# FFT-spectrum-analyser.net
KiCad netlist of a schematic drawn in EAGLE
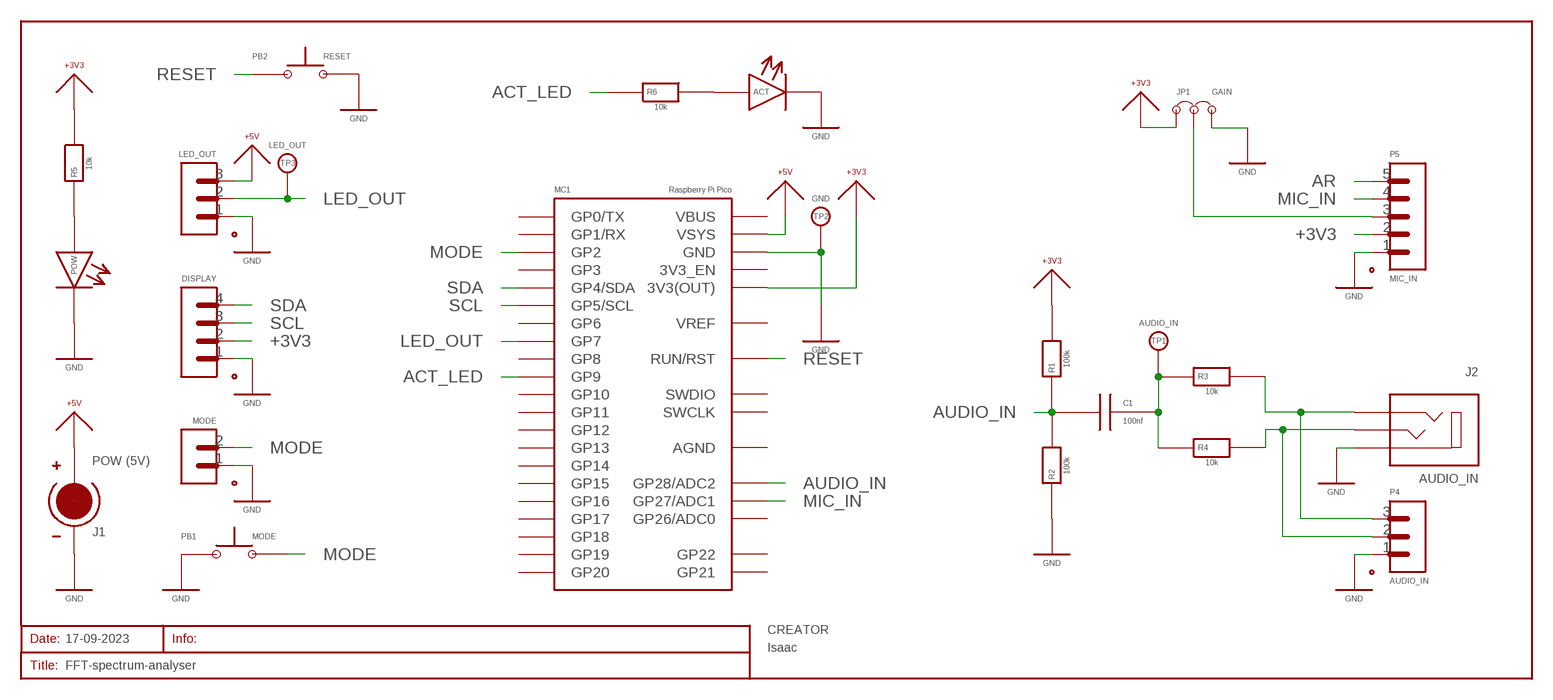
[diagram p0: schematic, sheet 1]

(export (version "E")
  (design (tool "Eeschema 10.0.6"))
  (components
    (comp (ref "ACT")
      (value "LED_3MM")
      (footprint "eagle-import:LED_3MM")
      (libsource (lib "eagle-import") (part "LED_3MM"))
    )
    (comp (ref "C1")
      (value "100nf")
      (footprint "eagle-import:CAPACITOR_UNPOLARISED_5.08MM")
      (libsource (lib "eagle-import") (part "CAPACITOR_UNPOLARISED_5.08MM"))
    )
    (comp (ref "CREATOR")
      (value "Isaac")
      (footprint "eagle-import:INFO_T")
      (libsource (lib "eagle-import") (part "INFO_T"))
    )
    (comp (ref "DISPLAY")
      (value "PORT_4-PIN_HEADER")
      (footprint "eagle-import:HEADER_4-PIN")
      (libsource (lib "eagle-import") (part "PORT_4-PIN_HEADER"))
    )
    (comp (ref "J1")
      (value "POW (5V)")
      (footprint "eagle-import:XH2.54_2-PIN")
      (libsource (lib "eagle-import") (part "DC_POWER_CENTER-POS_XH2.54"))
    )
    (comp (ref "J2")
      (value "AUDIO_IN")
      (footprint "eagle-import:3.5MM-JACK")
      (libsource (lib "eagle-import") (part "3.5MM-JACK_TYPE-A"))
    )
    (comp (ref "JP1")
      (value "GAIN")
      (footprint "eagle-import:HEADER_3-PIN_JUMPER")
      (libsource (lib "eagle-import") (part "JUMPER_3-WAY_HEADER"))
    )
    (comp (ref "LED_OUT")
      (value "PORT_3-PIN_XH2.54")
      (footprint "eagle-import:XH2.54_3-PIN")
      (libsource (lib "eagle-import") (part "PORT_3-PIN_XH2.54"))
    )
    (comp (ref "MC1")
      (value "RASPBERRY-PI-PICO_THT")
      (footprint "eagle-import:RASPBERRY-PI-PICO_THT")
      (libsource (lib "eagle-import") (part "RASPBERRY-PI-PICO_THT"))
    )
    (comp (ref "MODE")
      (value "PORT_2-PIN_XH2.54")
      (footprint "eagle-import:XH2.54_2-PIN")
      (libsource (lib "eagle-import") (part "PORT_2-PIN_XH2.54"))
    )
    (comp (ref "P4")
      (value "AUDIO_IN")
      (footprint "eagle-import:XH2.54_3-PIN")
      (libsource (lib "eagle-import") (part "PORT_3-PIN_XH2.54"))
    )
    (comp (ref "P5")
      (value "MIC_IN")
      (footprint "eagle-import:XH2.54_5-PIN")
      (libsource (lib "eagle-import") (part "PORT_5-PIN_XH2.54"))
    )
    (comp (ref "PB1")
      (value "MODE")
      (footprint "eagle-import:6MM_PUSHBUTTON")
      (libsource (lib "eagle-import") (part "MOMENTARY-SWITCH_NO_PUSHBUTTON"))
    )
    (comp (ref "PB2")
      (value "RESET")
      (footprint "eagle-import:6MM_PUSHBUTTON")
      (libsource (lib "eagle-import") (part "MOMENTARY-SWITCH_NO_PUSHBUTTON"))
    )
    (comp (ref "POW")
      (value "LED_3MM")
      (footprint "eagle-import:LED_3MM")
      (libsource (lib "eagle-import") (part "LED_3MM"))
    )
    (comp (ref "R1")
      (value "100k")
      (footprint "eagle-import:RESISTOR_10.16MM")
      (libsource (lib "eagle-import") (part "RESISTOR"))
    )
    (comp (ref "R2")
      (value "100k")
      (footprint "eagle-import:RESISTOR_10.16MM")
      (libsource (lib "eagle-import") (part "RESISTOR"))
    )
    (comp (ref "R3")
      (value "10k")
      (footprint "eagle-import:RESISTOR_10.16MM")
      (libsource (lib "eagle-import") (part "RESISTOR"))
    )
    (comp (ref "R4")
      (value "10k")
      (footprint "eagle-import:RESISTOR_10.16MM")
      (libsource (lib "eagle-import") (part "RESISTOR"))
    )
    (comp (ref "R5")
      (value "10k")
      (footprint "eagle-import:RESISTOR_10.16MM")
      (libsource (lib "eagle-import") (part "RESISTOR"))
    )
    (comp (ref "R6")
      (value "10k")
      (footprint "eagle-import:RESISTOR_10.16MM")
      (libsource (lib "eagle-import") (part "RESISTOR"))
    )
    (comp (ref "SCHEMATIC1")
      (value "17-09-2023")
      (footprint "eagle-import:SHEET")
      (libsource (lib "eagle-import") (part "SHEET"))
    )
    (comp (ref "TP1")
      (value "AUDIO_IN")
      (footprint "eagle-import:PAD_T")
      (libsource (lib "eagle-import") (part "TEST-POINT_T"))
    )
    (comp (ref "TP2")
      (value "GND")
      (footprint "eagle-import:PAD_T")
      (libsource (lib "eagle-import") (part "TEST-POINT_T"))
    )
    (comp (ref "TP3")
      (value "LED_OUT")
      (footprint "eagle-import:PAD_T")
      (libsource (lib "eagle-import") (part "TEST-POINT_T"))
    )
  )
  (nets
    (net (code "1") (name "+3V3") (class "Default")
      (node (ref "DISPLAY") (pin "2") (pinfunction "2_2") (pintype "bidirectional"))
      (node (ref "JP1") (pin "1") (pinfunction "1_1") (pintype "bidirectional"))
      (node (ref "MC1") (pin "36") (pinfunction "3V3(OUT)_36") (pintype "power_in"))
      (node (ref "P5") (pin "2") (pinfunction "2_2") (pintype "bidirectional"))
      (node (ref "R1") (pin "2") (pinfunction "2_2") (pintype "bidirectional"))
      (node (ref "R5") (pin "2") (pinfunction "2_2") (pintype "bidirectional"))
    )
    (net (code "2") (name "+5V") (class "Default")
      (node (ref "J1") (pin "2") (pinfunction "+_2") (pintype "output"))
      (node (ref "LED_OUT") (pin "3") (pinfunction "3_3") (pintype "bidirectional"))
      (node (ref "MC1") (pin "39") (pinfunction "VSYS_39") (pintype "bidirectional"))
    )
    (net (code "3") (name "/ACT_LED") (class "Default")
      (node (ref "MC1") (pin "12") (pinfunction "GP9_12") (pintype "bidirectional"))
      (node (ref "R6") (pin "1") (pinfunction "1_1") (pintype "bidirectional"))
    )
    (net (code "4") (name "/AGND") (class "Default")
      (node (ref "MC1") (pin "33") (pinfunction "AGND_33") (pintype "power_in"))
    )
    (net (code "5") (name "/AR") (class "Default")
      (node (ref "P5") (pin "5") (pinfunction "5_5") (pintype "bidirectional"))
    )
    (net (code "6") (name "/AUDIO_IN") (class "Default")
      (node (ref "C1") (pin "1") (pinfunction "1_1") (pintype "bidirectional"))
      (node (ref "MC1") (pin "34") (pinfunction "GP28/ADC2_34") (pintype "bidirectional"))
      (node (ref "R1") (pin "1") (pinfunction "1_1") (pintype "bidirectional"))
      (node (ref "R2") (pin "2") (pinfunction "2_2") (pintype "bidirectional"))
    )
    (net (code "7") (name "/LED_OUT") (class "Default")
      (node (ref "LED_OUT") (pin "2") (pinfunction "2_2") (pintype "bidirectional"))
      (node (ref "MC1") (pin "10") (pinfunction "GP7_10") (pintype "bidirectional"))
      (node (ref "TP3") (pin "1") (pinfunction "1_1") (pintype "bidirectional"))
    )
    (net (code "8") (name "/MIC_IN") (class "Default")
      (node (ref "MC1") (pin "32") (pinfunction "GP27/ADC1_32") (pintype "bidirectional"))
      (node (ref "P5") (pin "4") (pinfunction "4_4") (pintype "bidirectional"))
    )
    (net (code "9") (name "/MODE") (class "Default")
      (node (ref "MC1") (pin "4") (pinfunction "GP2_4") (pintype "bidirectional"))
      (node (ref "MODE") (pin "2") (pinfunction "2_2") (pintype "bidirectional"))
      (node (ref "PB1") (pin "2_A") (pinfunction "2_2_A") (pintype "bidirectional"))
      (node (ref "PB1") (pin "2_B") (pinfunction "2_2_B") (pintype "bidirectional"))
    )
    (net (code "10") (name "/RESET") (class "Default")
      (node (ref "MC1") (pin "30") (pinfunction "RUN/RST_30") (pintype "bidirectional"))
      (node (ref "PB2") (pin "1_A") (pinfunction "1_1_A") (pintype "bidirectional"))
      (node (ref "PB2") (pin "1_B") (pinfunction "1_1_B") (pintype "bidirectional"))
    )
    (net (code "11") (name "/SCL") (class "Default")
      (node (ref "DISPLAY") (pin "3") (pinfunction "3_3") (pintype "bidirectional"))
      (node (ref "MC1") (pin "7") (pinfunction "GP5/SCL_7") (pintype "bidirectional"))
    )
    (net (code "12") (name "/SDA") (class "Default")
      (node (ref "DISPLAY") (pin "4") (pinfunction "4_4") (pintype "bidirectional"))
      (node (ref "MC1") (pin "6") (pinfunction "GP4/SDA_6") (pintype "bidirectional"))
    )
    (net (code "13") (name "GND") (class "Default")
      (node (ref "ACT") (pin "-") (pinfunction "-_-") (pintype "output"))
      (node (ref "DISPLAY") (pin "1") (pinfunction "1_1") (pintype "bidirectional"))
      (node (ref "J1") (pin "1") (pinfunction "GND_1") (pintype "power_in"))
      (node (ref "J2") (pin "SLEEVE") (pinfunction "SLEEVE_SLEEVE") (pintype "power_in"))
      (node (ref "JP1") (pin "2") (pinfunction "3_2") (pintype "bidirectional"))
      (node (ref "LED_OUT") (pin "1") (pinfunction "1_1") (pintype "bidirectional"))
      (node (ref "MC1") (pin "13") (pinfunction "GND_13") (pintype "power_in"))
      (node (ref "MC1") (pin "18") (pinfunction "GND_18") (pintype "power_in"))
      (node (ref "MC1") (pin "23") (pinfunction "GND_23") (pintype "power_in"))
      (node (ref "MC1") (pin "28") (pinfunction "GND_28") (pintype "power_in"))
      (node (ref "MC1") (pin "3") (pinfunction "GND_3") (pintype "power_in"))
      (node (ref "MC1") (pin "38") (pinfunction "GND_38") (pintype "power_in"))
      (node (ref "MC1") (pin "8") (pinfunction "GND_8") (pintype "power_in"))
      (node (ref "MC1") (pin "D_GND") (pinfunction "GND_D_GND") (pintype "power_in"))
      (node (ref "MODE") (pin "1") (pinfunction "1_1") (pintype "bidirectional"))
      (node (ref "P4") (pin "1") (pinfunction "1_1") (pintype "bidirectional"))
      (node (ref "P5") (pin "1") (pinfunction "1_1") (pintype "bidirectional"))
      (node (ref "PB1") (pin "1_A") (pinfunction "1_1_A") (pintype "bidirectional"))
      (node (ref "PB1") (pin "1_B") (pinfunction "1_1_B") (pintype "bidirectional"))
      (node (ref "PB2") (pin "2_A") (pinfunction "2_2_A") (pintype "bidirectional"))
      (node (ref "PB2") (pin "2_B") (pinfunction "2_2_B") (pintype "bidirectional"))
      (node (ref "POW") (pin "-") (pinfunction "-_-") (pintype "output"))
      (node (ref "R2") (pin "1") (pinfunction "1_1") (pintype "bidirectional"))
      (node (ref "TP2") (pin "1") (pinfunction "1_1") (pintype "bidirectional"))
    )
    (net (code "14") (name "Net-(ACT-Pad+)") (class "Default")
      (node (ref "ACT") (pin "+") (pinfunction "+_+") (pintype "input"))
      (node (ref "R6") (pin "2") (pinfunction "2_2") (pintype "bidirectional"))
    )
    (net (code "15") (name "Net-(C1-Pad2)") (class "Default")
      (node (ref "C1") (pin "2") (pinfunction "2_2") (pintype "bidirectional"))
      (node (ref "R3") (pin "1") (pinfunction "1_1") (pintype "bidirectional"))
      (node (ref "R4") (pin "1") (pinfunction "1_1") (pintype "bidirectional"))
      (node (ref "TP1") (pin "1") (pinfunction "1_1") (pintype "bidirectional"))
    )
    (net (code "16") (name "Net-(J2-RING_R-PadRING_A)") (class "Default")
      (node (ref "J2") (pin "RING_A") (pinfunction "RING_R_RING_A") (pintype "output"))
      (node (ref "J2") (pin "RING_B") (pinfunction "RING_R_RING_B") (pintype "output"))
      (node (ref "P4") (pin "3") (pinfunction "3_3") (pintype "bidirectional"))
      (node (ref "R3") (pin "2") (pinfunction "2_2") (pintype "bidirectional"))
    )
    (net (code "17") (name "Net-(J2-TIP_L-PadTIP_A)") (class "Default")
      (node (ref "J2") (pin "TIP_A") (pinfunction "TIP_L_TIP_A") (pintype "output"))
      (node (ref "J2") (pin "TIP_B") (pinfunction "TIP_L_TIP_B") (pintype "output"))
      (node (ref "P4") (pin "2") (pinfunction "2_2") (pintype "bidirectional"))
      (node (ref "R4") (pin "2") (pinfunction "2_2") (pintype "bidirectional"))
    )
    (net (code "18") (name "Net-(JP1-2)") (class "Default")
      (node (ref "JP1") (pin "A") (pinfunction "2_A") (pintype "bidirectional"))
      (node (ref "P5") (pin "3") (pinfunction "3_3") (pintype "bidirectional"))
    )
    (net (code "19") (name "Net-(POW-Pad+)") (class "Default")
      (node (ref "POW") (pin "+") (pinfunction "+_+") (pintype "input"))
      (node (ref "R5") (pin "1") (pinfunction "1_1") (pintype "bidirectional"))
    )
    (net (code "20") (name "unconnected-(MC1-3V3_EN-Pad37)") (class "Default")
      (node (ref "MC1") (pin "37") (pinfunction "3V3_EN_37") (pintype "bidirectional"))
    )
    (net (code "21") (name "unconnected-(MC1-GP0{slash}TX-Pad1)") (class "Default")
      (node (ref "MC1") (pin "1") (pinfunction "GP0/TX_1") (pintype "bidirectional"))
    )
    (net (code "22") (name "unconnected-(MC1-GP1{slash}RX-Pad2)") (class "Default")
      (node (ref "MC1") (pin "2") (pinfunction "GP1/RX_2") (pintype "bidirectional"))
    )
    (net (code "23") (name "unconnected-(MC1-GP3-Pad5)") (class "Default")
      (node (ref "MC1") (pin "5") (pinfunction "GP3_5") (pintype "bidirectional"))
    )
    (net (code "24") (name "unconnected-(MC1-GP6-Pad9)") (class "Default")
      (node (ref "MC1") (pin "9") (pinfunction "GP6_9") (pintype "bidirectional"))
    )
    (net (code "25") (name "unconnected-(MC1-GP8-Pad11)") (class "Default")
      (node (ref "MC1") (pin "11") (pinfunction "GP8_11") (pintype "bidirectional"))
    )
    (net (code "26") (name "unconnected-(MC1-GP10-Pad14)") (class "Default")
      (node (ref "MC1") (pin "14") (pinfunction "GP10_14") (pintype "bidirectional"))
    )
    (net (code "27") (name "unconnected-(MC1-GP11-Pad15)") (class "Default")
      (node (ref "MC1") (pin "15") (pinfunction "GP11_15") (pintype "bidirectional"))
    )
    (net (code "28") (name "unconnected-(MC1-GP12-Pad16)") (class "Default")
      (node (ref "MC1") (pin "16") (pinfunction "GP12_16") (pintype "bidirectional"))
    )
    (net (code "29") (name "unconnected-(MC1-GP13-Pad17)") (class "Default")
      (node (ref "MC1") (pin "17") (pinfunction "GP13_17") (pintype "bidirectional"))
    )
    (net (code "30") (name "unconnected-(MC1-GP14-Pad19)") (class "Default")
      (node (ref "MC1") (pin "19") (pinfunction "GP14_19") (pintype "bidirectional"))
    )
    (net (code "31") (name "unconnected-(MC1-GP15-Pad20)") (class "Default")
      (node (ref "MC1") (pin "20") (pinfunction "GP15_20") (pintype "bidirectional"))
    )
    (net (code "32") (name "unconnected-(MC1-GP16-Pad21)") (class "Default")
      (node (ref "MC1") (pin "21") (pinfunction "GP16_21") (pintype "bidirectional"))
    )
    (net (code "33") (name "unconnected-(MC1-GP17-Pad22)") (class "Default")
      (node (ref "MC1") (pin "22") (pinfunction "GP17_22") (pintype "bidirectional"))
    )
    (net (code "34") (name "unconnected-(MC1-GP18-Pad24)") (class "Default")
      (node (ref "MC1") (pin "24") (pinfunction "GP18_24") (pintype "bidirectional"))
    )
    (net (code "35") (name "unconnected-(MC1-GP19-Pad25)") (class "Default")
      (node (ref "MC1") (pin "25") (pinfunction "GP19_25") (pintype "bidirectional"))
    )
    (net (code "36") (name "unconnected-(MC1-GP20-Pad26)") (class "Default")
      (node (ref "MC1") (pin "26") (pinfunction "GP20_26") (pintype "bidirectional"))
    )
    (net (code "37") (name "unconnected-(MC1-GP21-Pad27)") (class "Default")
      (node (ref "MC1") (pin "27") (pinfunction "GP21_27") (pintype "bidirectional"))
    )
    (net (code "38") (name "unconnected-(MC1-GP22-Pad29)") (class "Default")
      (node (ref "MC1") (pin "29") (pinfunction "GP22_29") (pintype "bidirectional"))
    )
    (net (code "39") (name "unconnected-(MC1-GP26{slash}ADC0-Pad31)") (class "Default")
      (node (ref "MC1") (pin "31") (pinfunction "GP26/ADC0_31") (pintype "bidirectional"))
    )
    (net (code "40") (name "unconnected-(MC1-PadSWCLK)") (class "Default")
      (node (ref "MC1") (pin "SWCLK") (pinfunction "SWCLK_SWCLK") (pintype "bidirectional"))
    )
    (net (code "41") (name "unconnected-(MC1-PadSWDIO)") (class "Default")
      (node (ref "MC1") (pin "SWDIO") (pinfunction "SWDIO_SWDIO") (pintype "bidirectional"))
    )
    (net (code "42") (name "unconnected-(MC1-VBUS-Pad40)") (class "Default")
      (node (ref "MC1") (pin "40") (pinfunction "VBUS_40") (pintype "bidirectional"))
    )
    (net (code "43") (name "unconnected-(MC1-VREF-Pad35)") (class "Default")
      (node (ref "MC1") (pin "35") (pinfunction "VREF_35") (pintype "bidirectional"))
    )
  )
)
